# V2_0.net
KiCad netlist of a schematic drawn in Altium Designer
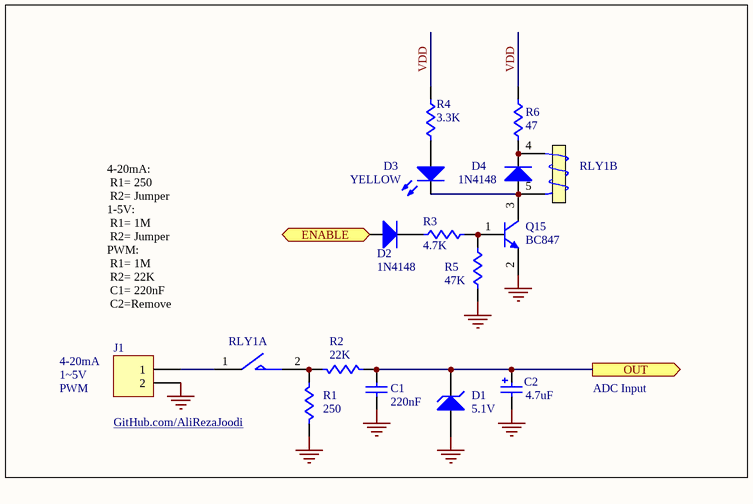
[diagram p0: V2.0.SchDoc]

(export (version "E")
  (design (tool "Eeschema 10.0.6"))
  (components
    (comp (ref "C1")
      (value "220nF")
      (footprint "CAPNTO2.54-3.05x1.78A")
      (description "Capacitor")
      (fields (field (name "MANUFACTURER") "Generic Components") (field (name "PUBLISHER") "Altium Limited"))
      (libsource (lib "Miscellaneous Devices") (part "Cap"))
    )
    (comp (ref "C2")
      (value "4.7uF")
      (footprint "CAPPR2.5-6.3x5")
      (description "Polarized Capacitor (Radial)")
      (fields (field (name "MANUFACTURER") "Generic Components") (field (name "PUBLISHER") "Altium Limited"))
      (libsource (lib "Miscellaneous Devices") (part "Cap Pol1"))
    )
    (comp (ref "D1")
      (value "5.1V")
      (footprint "DIODE0.4_Glass")
      (description "Zener Diode")
      (fields (field (name "MANUFACTURER") "Generic Components") (field (name "PUBLISHER") "Altium Limited"))
      (libsource (lib "Miscellaneous Devices") (part "D Zener"))
    )
    (comp (ref "D2")
      (value "1N4148")
      (footprint "0805_Diode")
      (description "Default Diode")
      (fields
        (field (name "MANUFACTURER") "Generic Components")
        (field (name "Comment") "Diode")
        (field (name "PUBLISHER") "Altium Limited")
      )
      (libsource (lib "Miscellaneous Devices") (part "Diode"))
    )
    (comp (ref "D3")
      (value "YELLOW")
      (footprint "0805_Diode")
      (description "Typical INFRARED GaAs LED")
      (fields (field (name "MANUFACTURER") "Generic Components") (field (name "PUBLISHER") "Altium Limited"))
      (libsource (lib "Miscellaneous Devices") (part "LED"))
    )
    (comp (ref "D4")
      (value "1N4148")
      (footprint "0805_Diode")
      (description "Default Diode")
      (fields
        (field (name "MANUFACTURER") "Generic Components")
        (field (name "Comment") "Diode")
        (field (name "PUBLISHER") "Altium Limited")
      )
      (libsource (lib "Miscellaneous Devices") (part "Diode"))
    )
    (comp (ref "J1")
      (value "Header 2")
      (footprint "Fonics_2PIN_1")
      (description "Header, 2-Pin")
      (fields (field (name "PUBLISHER") "Altium Limited"))
      (libsource (lib "Miscellaneous Connectors") (part "Header 2"))
    )
    (comp (ref "Q1")
      (value "Q15")
      (footprint "SOT23-3N")
      (description "Silicon Bipolar Transistor")
      (fields (field (name "ALTIUM_VALUE") "BC847"))
      (libsource (lib "my Libraries") (part "BC847"))
    )
    (comp (ref "R1")
      (value "250")
      (footprint "AXIAL-0.4")
      (description "Resistor")
      (fields (field (name "MANUFACTURER") "Generic Components") (field (name "PUBLISHER") "Altium Limited"))
      (libsource (lib "Miscellaneous Devices") (part "Res1"))
    )
    (comp (ref "R2")
      (value "22K")
      (footprint "AXIAL-0.4")
      (description "Resistor")
      (fields (field (name "MANUFACTURER") "Generic Components") (field (name "PUBLISHER") "Altium Limited"))
      (libsource (lib "Miscellaneous Devices") (part "Res1"))
    )
    (comp (ref "R3")
      (value "4.7K")
      (footprint "0805")
      (description "Resistor")
      (fields
        (field (name "MANUFACTURER") "Generic Components")
        (field (name "Comment") "Res1")
        (field (name "PUBLISHER") "Altium Limited")
      )
      (libsource (lib "Miscellaneous Devices") (part "Res1"))
    )
    (comp (ref "R4")
      (value "3.3K")
      (footprint "0805")
      (description "Resistor")
      (fields
        (field (name "MANUFACTURER") "Generic Components")
        (field (name "Comment") "Res1")
        (field (name "PUBLISHER") "Altium Limited")
      )
      (libsource (lib "Miscellaneous Devices") (part "Res1"))
    )
    (comp (ref "R5")
      (value "47K")
      (footprint "0805")
      (description "Resistor")
      (fields
        (field (name "MANUFACTURER") "Generic Components")
        (field (name "Comment") "Res1")
        (field (name "PUBLISHER") "Altium Limited")
      )
      (libsource (lib "Miscellaneous Devices") (part "Res1"))
    )
    (comp (ref "R6")
      (value "47")
      (footprint "RESC3216N")
      (description "Resistor")
      (fields (field (name "MANUFACTURER") "Generic Components") (field (name "PUBLISHER") "Altium Limited"))
      (libsource (lib "Miscellaneous Devices") (part "Res1"))
    )
    (comp (ref "RLY1")
      (value "RELAU")
      (footprint "RELAY-SPDT-2")
      (fields (field (name "PUBLISHER") "Altium Limited"))
      (libsource (lib "my Libraries") (part "RELAY-NY12W-K"))
    )
  )
  (nets
    (net (code "1") (name "/ENABLE") (class "Default")
      (node (ref "D2") (pin "1") (pinfunction "A_1") (pintype "passive"))
    )
    (net (code "2") (name "/OUT") (class "Default")
      (node (ref "C1") (pin "2") (pinfunction "2_2") (pintype "passive"))
      (node (ref "C2") (pin "1") (pinfunction "1_1") (pintype "passive"))
      (node (ref "D1") (pin "2") (pinfunction "K_2") (pintype "passive"))
      (node (ref "R2") (pin "2") (pinfunction "2_2") (pintype "passive"))
    )
    (net (code "3") (name "/VDD") (class "Default")
      (node (ref "R4") (pin "1") (pinfunction "1_1") (pintype "passive"))
      (node (ref "R6") (pin "1") (pinfunction "1_1") (pintype "passive"))
    )
    (net (code "4") (name "GND") (class "Default")
      (node (ref "C1") (pin "1") (pinfunction "1_1") (pintype "passive"))
      (node (ref "C2") (pin "2") (pinfunction "2_2") (pintype "passive"))
      (node (ref "D1") (pin "1") (pinfunction "A_1") (pintype "passive"))
      (node (ref "J1") (pin "2") (pinfunction "2_2") (pintype "passive"))
      (node (ref "Q1") (pin "2") (pinfunction "E_2") (pintype "passive"))
      (node (ref "R1") (pin "2") (pinfunction "2_2") (pintype "passive"))
      (node (ref "R5") (pin "1") (pinfunction "1_1") (pintype "passive"))
    )
    (net (code "5") (name "Net-(D2-K)") (class "Default")
      (node (ref "D2") (pin "2") (pinfunction "K_2") (pintype "passive"))
      (node (ref "R3") (pin "1") (pinfunction "1_1") (pintype "passive"))
    )
    (net (code "6") (name "Net-(D3-A)") (class "Default")
      (node (ref "D3") (pin "1") (pinfunction "A_1") (pintype "passive"))
      (node (ref "R4") (pin "2") (pinfunction "2_2") (pintype "passive"))
    )
    (net (code "7") (name "Net-(D3-K)") (class "Default")
      (node (ref "D3") (pin "2") (pinfunction "K_2") (pintype "passive"))
      (node (ref "D4") (pin "1") (pinfunction "A_1") (pintype "passive"))
      (node (ref "Q1") (pin "3") (pinfunction "C_3") (pintype "passive"))
      (node (ref "RLY1") (pin "5") (pinfunction "T2_5") (pintype "passive"))
    )
    (net (code "8") (name "Net-(D4-K)") (class "Default")
      (node (ref "D4") (pin "2") (pinfunction "K_2") (pintype "passive"))
      (node (ref "R6") (pin "2") (pinfunction "2_2") (pintype "passive"))
      (node (ref "RLY1") (pin "4") (pinfunction "T1_4") (pintype "passive"))
    )
    (net (code "9") (name "Net-(Q1-B)") (class "Default")
      (node (ref "Q1") (pin "1") (pinfunction "B_1") (pintype "passive"))
      (node (ref "R3") (pin "2") (pinfunction "2_2") (pintype "passive"))
      (node (ref "R5") (pin "2") (pinfunction "2_2") (pintype "passive"))
    )
    (net (code "10") (name "Net-(RLY1A-COM)") (class "Default")
      (node (ref "J1") (pin "1") (pinfunction "1_1") (pintype "passive"))
      (node (ref "RLY1") (pin "1") (pinfunction "COM_1") (pintype "passive"))
    )
    (net (code "11") (name "Net-(RLY1A-NO)") (class "Default")
      (node (ref "R1") (pin "1") (pinfunction "1_1") (pintype "passive"))
      (node (ref "R2") (pin "1") (pinfunction "1_1") (pintype "passive"))
      (node (ref "RLY1") (pin "2") (pinfunction "NO_2") (pintype "passive"))
    )
  )
)
